# APM32F030K8T6.net
KiCad netlist of a schematic drawn in Altium Designer
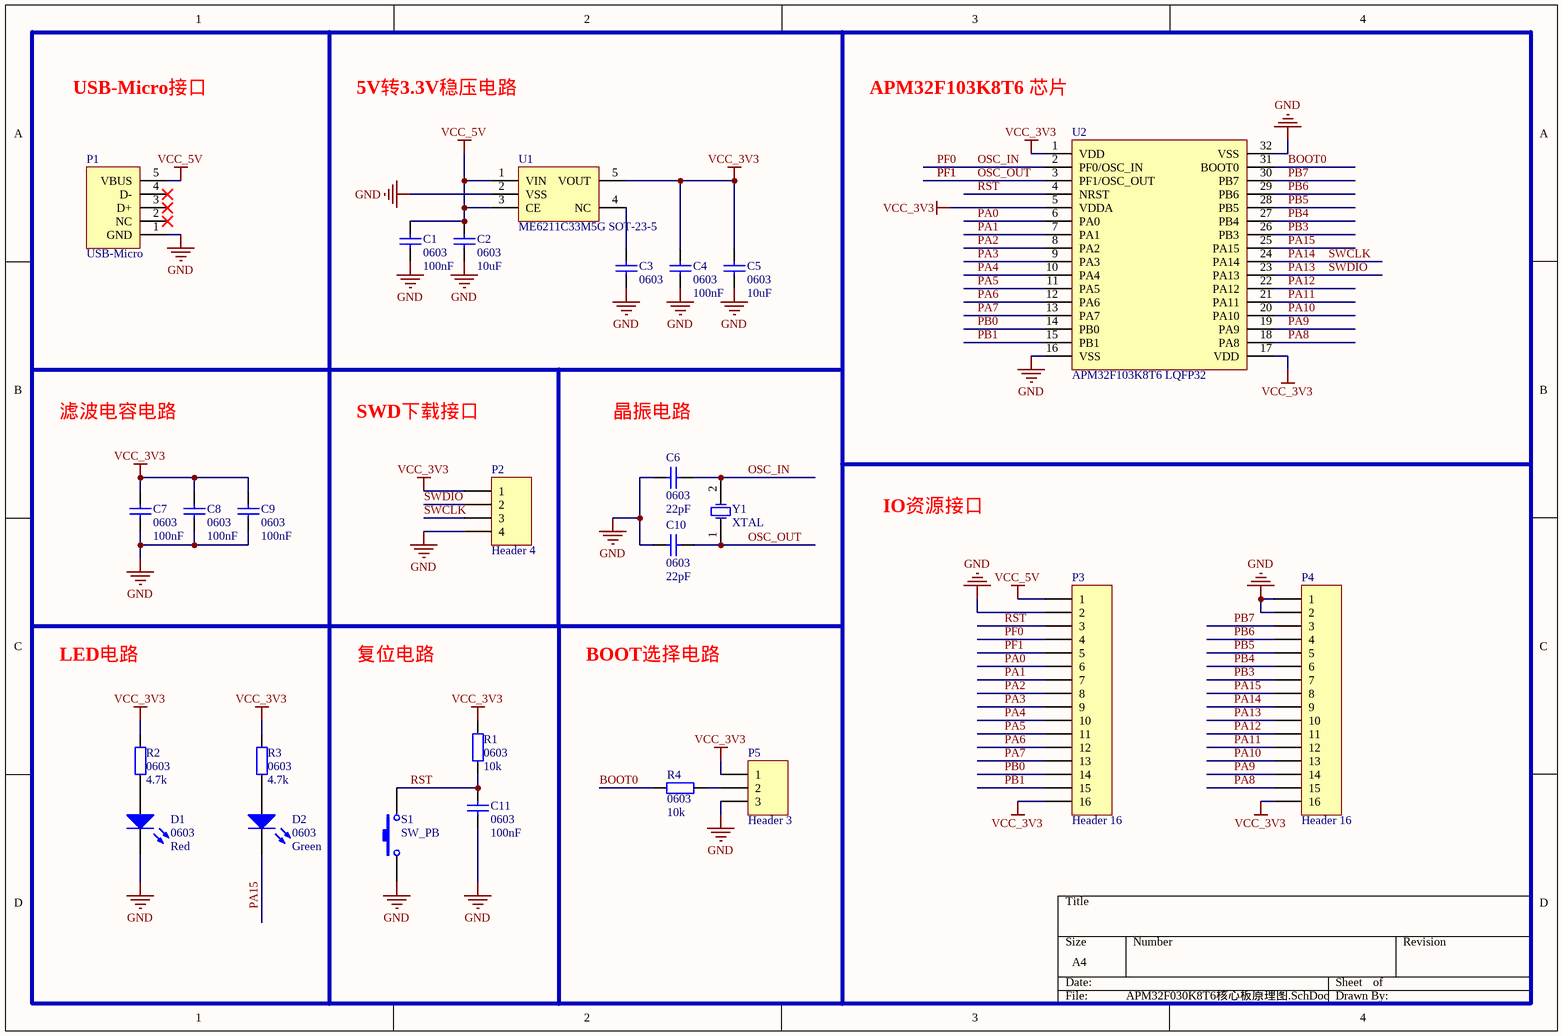
[diagram p0: APM32F030K8T6核心板原理图.SchDoc]

(export (version "E")
  (design (tool "Eeschema 10.0.6"))
  (components
    (comp (ref "C1")
      (value "100nF")
      (footprint "0603")
      (description "Capacitor 0603")
      (fields (field (name "Comment") "Cap 0603"))
      (libsource (lib "Schlib1") (part "Cap 0603"))
    )
    (comp (ref "C2")
      (value "10uF")
      (footprint "0603")
      (description "Capacitor 0603")
      (fields (field (name "Comment") "Cap 0603"))
      (libsource (lib "Schlib1") (part "Cap 0603"))
    )
    (comp (ref "C3")
      (value "Cap 0603")
      (footprint "0603")
      (description "Capacitor 0603")
      (libsource (lib "Schlib1") (part "Cap 0603"))
    )
    (comp (ref "C4")
      (value "100nF")
      (footprint "0603")
      (description "Capacitor 0603")
      (fields (field (name "Comment") "Cap 0603"))
      (libsource (lib "Schlib1") (part "Cap 0603"))
    )
    (comp (ref "C5")
      (value "10uF")
      (footprint "0603")
      (description "Capacitor 0603")
      (fields (field (name "Comment") "Cap 0603"))
      (libsource (lib "Schlib1") (part "Cap 0603"))
    )
    (comp (ref "C6")
      (value "22pF")
      (footprint "0603")
      (description "Capacitor 0603")
      (fields (field (name "Comment") "Cap 0603"))
      (libsource (lib "Schlib1") (part "Cap 0603"))
    )
    (comp (ref "C7")
      (value "100nF")
      (footprint "0603")
      (description "Capacitor 0603")
      (fields (field (name "Comment") "Cap 0603"))
      (libsource (lib "Schlib1") (part "Cap 0603"))
    )
    (comp (ref "C8")
      (value "100nF")
      (footprint "0603")
      (description "Capacitor 0603")
      (fields (field (name "Comment") "Cap 0603"))
      (libsource (lib "Schlib1") (part "Cap 0603"))
    )
    (comp (ref "C9")
      (value "100nF")
      (footprint "0603")
      (description "Capacitor 0603")
      (fields (field (name "Comment") "Cap 0603"))
      (libsource (lib "Schlib1") (part "Cap 0603"))
    )
    (comp (ref "C10")
      (value "22pF")
      (footprint "0603")
      (description "Capacitor 0603")
      (fields (field (name "Comment") "Cap 0603"))
      (libsource (lib "Schlib1") (part "Cap 0603"))
    )
    (comp (ref "C11")
      (value "100nF")
      (footprint "0603")
      (description "Capacitor 0603")
      (fields (field (name "Comment") "Cap 0603"))
      (libsource (lib "Schlib1") (part "Cap 0603"))
    )
    (comp (ref "D1")
      (value "Red")
      (footprint "0603")
      (description "LED 0603")
      (libsource (lib "Schlib1") (part "LED 0603"))
    )
    (comp (ref "D2")
      (value "Green")
      (footprint "0603")
      (description "LED 0603")
      (libsource (lib "Schlib1") (part "LED 0603"))
    )
    (comp (ref "P1")
      (value "USB-Micro")
      (footprint "USB Micro")
      (libsource (lib "Schlib1") (part "USB-Micro"))
    )
    (comp (ref "P2")
      (value "Header 4")
      (footprint "HDR1X4")
      (description "Header, 4-Pin")
      (fields (field (name "PUBLISHER") "Altium Limited"))
      (libsource (lib "Miscellaneous Connectors") (part "Header 4"))
    )
    (comp (ref "P3")
      (value "Header 16")
      (footprint "HDR1X16")
      (description "Header, 16-Pin")
      (fields (field (name "PUBLISHER") "Altium Limited"))
      (libsource (lib "Miscellaneous Connectors") (part "Header 16"))
    )
    (comp (ref "P4")
      (value "Header 16")
      (footprint "HDR1X16")
      (description "Header, 16-Pin")
      (fields (field (name "PUBLISHER") "Altium Limited"))
      (libsource (lib "Miscellaneous Connectors") (part "Header 16"))
    )
    (comp (ref "P5")
      (value "Header 3")
      (footprint "HDR1X3")
      (description "Header, 3-Pin")
      (fields (field (name "PUBLISHER") "Altium Limited"))
      (libsource (lib "Miscellaneous Connectors") (part "Header 3"))
    )
    (comp (ref "R1")
      (value "10k")
      (footprint "0603")
      (description "Resistor 0603")
      (fields (field (name "Comment") "Res 0603"))
      (libsource (lib "") (part "Res 0603_2"))
    )
    (comp (ref "R2")
      (value "4.7k")
      (footprint "0603")
      (description "Resistor 0603")
      (fields (field (name "Comment") "Res 0603"))
      (libsource (lib "") (part "Res 0603_1"))
    )
    (comp (ref "R3")
      (value "4.7k")
      (footprint "0603")
      (description "Resistor 0603")
      (fields (field (name "Comment") "Res 0603"))
      (libsource (lib "") (part "Res 0603_1"))
    )
    (comp (ref "R4")
      (value "10k")
      (footprint "0603")
      (description "Resistor 0603")
      (fields (field (name "Comment") "Res 0603"))
      (libsource (lib "Schlib1") (part "Res 0603"))
    )
    (comp (ref "S1") (value "SW_PB") (footprint "SW-2Pin") (libsource (lib "Schlib1") (part "SW_PB")))
    (comp (ref "U1")
      (value "ME6211C33M5G SOT-23-5")
      (footprint "SOT-23-5")
      (libsource (lib "Schlib1") (part "ME6211C33M5G"))
    )
    (comp (ref "U2")
      (value "APM32F103K8T6 LQFP32")
      (footprint "QFP32_M")
      (description "STM32F030K6T6 LQFP32")
      (libsource (lib "Schlib1") (part "STM32F030K6T6 LQFP32"))
    )
    (comp (ref "Y1")
      (value "XTAL")
      (footprint "XTAL_5032")
      (description "XTAL 8MHZ")
      (libsource (lib "Schlib1") (part "XTAL 8MHZ"))
    )
  )
  (nets
    (net (code "1") (name "/BOOT0") (class "Default")
      (node (ref "R4") (pin "1") (pinfunction "1_1") (pintype "passive"))
      (node (ref "U2") (pin "31") (pinfunction "BOOT0_31") (pintype "power_in"))
    )
    (net (code "2") (name "/OSC_IN") (class "Default")
      (node (ref "C6") (pin "1") (pinfunction "1_1") (pintype "passive"))
      (node (ref "P3") (pin "4") (pinfunction "4_4") (pintype "passive"))
      (node (ref "U2") (pin "2") (pinfunction "PF0/OSC_IN_2") (pintype "power_in"))
      (node (ref "Y1") (pin "2") (pinfunction "OSC2_2") (pintype "passive"))
    )
    (net (code "3") (name "/OSC_OUT") (class "Default")
      (node (ref "C10") (pin "1") (pinfunction "1_1") (pintype "passive"))
      (node (ref "P3") (pin "5") (pinfunction "5_5") (pintype "passive"))
      (node (ref "U2") (pin "3") (pinfunction "PF1/OSC_OUT_3") (pintype "power_in"))
      (node (ref "Y1") (pin "1") (pinfunction "OSC1_1") (pintype "passive"))
    )
    (net (code "4") (name "/PA0") (class "Default")
      (node (ref "P3") (pin "6") (pinfunction "6_6") (pintype "passive"))
      (node (ref "U2") (pin "6") (pinfunction "PA0_6") (pintype "power_in"))
    )
    (net (code "5") (name "/PA1") (class "Default")
      (node (ref "P3") (pin "7") (pinfunction "7_7") (pintype "passive"))
      (node (ref "U2") (pin "7") (pinfunction "PA1_7") (pintype "power_in"))
    )
    (net (code "6") (name "/PA2") (class "Default")
      (node (ref "P3") (pin "8") (pinfunction "8_8") (pintype "passive"))
      (node (ref "U2") (pin "8") (pinfunction "PA2_8") (pintype "power_in"))
    )
    (net (code "7") (name "/PA3") (class "Default")
      (node (ref "P3") (pin "9") (pinfunction "9_9") (pintype "passive"))
      (node (ref "U2") (pin "9") (pinfunction "PA3_9") (pintype "power_in"))
    )
    (net (code "8") (name "/PA4") (class "Default")
      (node (ref "P3") (pin "10") (pinfunction "10_10") (pintype "passive"))
      (node (ref "U2") (pin "10") (pinfunction "PA4_10") (pintype "power_in"))
    )
    (net (code "9") (name "/PA5") (class "Default")
      (node (ref "P3") (pin "11") (pinfunction "11_11") (pintype "passive"))
      (node (ref "U2") (pin "11") (pinfunction "PA5_11") (pintype "power_in"))
    )
    (net (code "10") (name "/PA6") (class "Default")
      (node (ref "P3") (pin "12") (pinfunction "12_12") (pintype "passive"))
      (node (ref "U2") (pin "12") (pinfunction "PA6_12") (pintype "power_in"))
    )
    (net (code "11") (name "/PA7") (class "Default")
      (node (ref "P3") (pin "13") (pinfunction "13_13") (pintype "passive"))
      (node (ref "U2") (pin "13") (pinfunction "PA7_13") (pintype "power_in"))
    )
    (net (code "12") (name "/PA8") (class "Default")
      (node (ref "P4") (pin "15") (pinfunction "15_15") (pintype "passive"))
      (node (ref "U2") (pin "18") (pinfunction "PA8_18") (pintype "power_in"))
    )
    (net (code "13") (name "/PA9") (class "Default")
      (node (ref "P4") (pin "14") (pinfunction "14_14") (pintype "passive"))
      (node (ref "U2") (pin "19") (pinfunction "PA9_19") (pintype "power_in"))
    )
    (net (code "14") (name "/PA10") (class "Default")
      (node (ref "P4") (pin "13") (pinfunction "13_13") (pintype "passive"))
      (node (ref "U2") (pin "20") (pinfunction "PA10_20") (pintype "power_in"))
    )
    (net (code "15") (name "/PA11") (class "Default")
      (node (ref "P4") (pin "12") (pinfunction "12_12") (pintype "passive"))
      (node (ref "U2") (pin "21") (pinfunction "PA11_21") (pintype "power_in"))
    )
    (net (code "16") (name "/PA12") (class "Default")
      (node (ref "P4") (pin "11") (pinfunction "11_11") (pintype "passive"))
      (node (ref "U2") (pin "22") (pinfunction "PA12_22") (pintype "power_in"))
    )
    (net (code "17") (name "/PA13") (class "Default")
      (node (ref "P2") (pin "2") (pinfunction "2_2") (pintype "passive"))
      (node (ref "P4") (pin "10") (pinfunction "10_10") (pintype "passive"))
      (node (ref "U2") (pin "23") (pinfunction "PA13_23") (pintype "power_in"))
    )
    (net (code "18") (name "/PA14") (class "Default")
      (node (ref "P2") (pin "3") (pinfunction "3_3") (pintype "passive"))
      (node (ref "P4") (pin "9") (pinfunction "9_9") (pintype "passive"))
      (node (ref "U2") (pin "24") (pinfunction "PA14_24") (pintype "power_in"))
    )
    (net (code "19") (name "/PA15") (class "Default")
      (node (ref "D2") (pin "2") (pinfunction "K_2") (pintype "passive"))
      (node (ref "P4") (pin "8") (pinfunction "8_8") (pintype "passive"))
      (node (ref "U2") (pin "25") (pinfunction "PA15_25") (pintype "power_in"))
    )
    (net (code "20") (name "/PB0") (class "Default")
      (node (ref "P3") (pin "14") (pinfunction "14_14") (pintype "passive"))
      (node (ref "U2") (pin "14") (pinfunction "PB0_14") (pintype "power_in"))
    )
    (net (code "21") (name "/PB1") (class "Default")
      (node (ref "P3") (pin "15") (pinfunction "15_15") (pintype "passive"))
      (node (ref "U2") (pin "15") (pinfunction "PB1_15") (pintype "power_in"))
    )
    (net (code "22") (name "/PB3") (class "Default")
      (node (ref "P4") (pin "7") (pinfunction "7_7") (pintype "passive"))
      (node (ref "U2") (pin "26") (pinfunction "PB3_26") (pintype "power_in"))
    )
    (net (code "23") (name "/PB4") (class "Default")
      (node (ref "P4") (pin "6") (pinfunction "6_6") (pintype "passive"))
      (node (ref "U2") (pin "27") (pinfunction "PB4_27") (pintype "power_in"))
    )
    (net (code "24") (name "/PB5") (class "Default")
      (node (ref "P4") (pin "5") (pinfunction "5_5") (pintype "passive"))
      (node (ref "U2") (pin "28") (pinfunction "PB5_28") (pintype "power_in"))
    )
    (net (code "25") (name "/PB6") (class "Default")
      (node (ref "P4") (pin "4") (pinfunction "4_4") (pintype "passive"))
      (node (ref "U2") (pin "29") (pinfunction "PB6_29") (pintype "power_in"))
    )
    (net (code "26") (name "/PB7") (class "Default")
      (node (ref "P4") (pin "3") (pinfunction "3_3") (pintype "passive"))
      (node (ref "U2") (pin "30") (pinfunction "PB7_30") (pintype "power_in"))
    )
    (net (code "27") (name "/RST") (class "Default")
      (node (ref "C11") (pin "2") (pinfunction "2_2") (pintype "passive"))
      (node (ref "P3") (pin "3") (pinfunction "3_3") (pintype "passive"))
      (node (ref "R1") (pin "1") (pinfunction "1_1") (pintype "passive"))
      (node (ref "S1") (pin "2") (pinfunction "2_2") (pintype "passive"))
      (node (ref "U2") (pin "4") (pinfunction "NRST_4") (pintype "power_in"))
    )
    (net (code "28") (name "GND") (class "Default")
      (node (ref "C1") (pin "1") (pinfunction "1_1") (pintype "passive"))
      (node (ref "C10") (pin "2") (pinfunction "2_2") (pintype "passive"))
      (node (ref "C11") (pin "1") (pinfunction "1_1") (pintype "passive"))
      (node (ref "C2") (pin "1") (pinfunction "1_1") (pintype "passive"))
      (node (ref "C3") (pin "1") (pinfunction "1_1") (pintype "passive"))
      (node (ref "C4") (pin "1") (pinfunction "1_1") (pintype "passive"))
      (node (ref "C5") (pin "1") (pinfunction "1_1") (pintype "passive"))
      (node (ref "C6") (pin "2") (pinfunction "2_2") (pintype "passive"))
      (node (ref "C7") (pin "1") (pinfunction "1_1") (pintype "passive"))
      (node (ref "C8") (pin "1") (pinfunction "1_1") (pintype "passive"))
      (node (ref "C9") (pin "1") (pinfunction "1_1") (pintype "passive"))
      (node (ref "D1") (pin "2") (pinfunction "K_2") (pintype "passive"))
      (node (ref "P1") (pin "1") (pinfunction "GND_1") (pintype "power_in"))
      (node (ref "P2") (pin "4") (pinfunction "4_4") (pintype "passive"))
      (node (ref "P3") (pin "2") (pinfunction "2_2") (pintype "passive"))
      (node (ref "P4") (pin "1") (pinfunction "1_1") (pintype "passive"))
      (node (ref "P4") (pin "2") (pinfunction "2_2") (pintype "passive"))
      (node (ref "P5") (pin "3") (pinfunction "3_3") (pintype "passive"))
      (node (ref "S1") (pin "1") (pinfunction "1_1") (pintype "passive"))
      (node (ref "U1") (pin "2") (pinfunction "VSS_2") (pintype "power_in"))
      (node (ref "U2") (pin "16") (pinfunction "VSS_16") (pintype "power_in"))
      (node (ref "U2") (pin "32") (pinfunction "VSS_32") (pintype "power_in"))
    )
    (net (code "29") (name "Net-(D1-A)") (class "Default")
      (node (ref "D1") (pin "1") (pinfunction "A_1") (pintype "passive"))
      (node (ref "R2") (pin "2") (pinfunction "2_2") (pintype "passive"))
    )
    (net (code "30") (name "Net-(D2-A)") (class "Default")
      (node (ref "D2") (pin "1") (pinfunction "A_1") (pintype "passive"))
      (node (ref "R3") (pin "2") (pinfunction "2_2") (pintype "passive"))
    )
    (net (code "31") (name "Net-(P5-Pad2)") (class "Default")
      (node (ref "P5") (pin "2") (pinfunction "2_2") (pintype "passive"))
      (node (ref "R4") (pin "2") (pinfunction "2_2") (pintype "passive"))
    )
    (net (code "32") (name "Net-(U1-NC)") (class "Default")
      (node (ref "C3") (pin "2") (pinfunction "2_2") (pintype "passive"))
      (node (ref "U1") (pin "4") (pinfunction "NC_4") (pintype "power_in"))
    )
    (net (code "33") (name "VCC_3V3") (class "Default")
      (node (ref "C4") (pin "2") (pinfunction "2_2") (pintype "passive"))
      (node (ref "C5") (pin "2") (pinfunction "2_2") (pintype "passive"))
      (node (ref "C7") (pin "2") (pinfunction "2_2") (pintype "passive"))
      (node (ref "C8") (pin "2") (pinfunction "2_2") (pintype "passive"))
      (node (ref "C9") (pin "2") (pinfunction "2_2") (pintype "passive"))
      (node (ref "P2") (pin "1") (pinfunction "1_1") (pintype "passive"))
      (node (ref "P3") (pin "16") (pinfunction "16_16") (pintype "passive"))
      (node (ref "P4") (pin "16") (pinfunction "16_16") (pintype "passive"))
      (node (ref "P5") (pin "1") (pinfunction "1_1") (pintype "passive"))
      (node (ref "R1") (pin "2") (pinfunction "2_2") (pintype "passive"))
      (node (ref "R2") (pin "1") (pinfunction "1_1") (pintype "passive"))
      (node (ref "R3") (pin "1") (pinfunction "1_1") (pintype "passive"))
      (node (ref "U1") (pin "5") (pinfunction "VOUT_5") (pintype "power_in"))
      (node (ref "U2") (pin "1") (pinfunction "VDD_1") (pintype "power_in"))
      (node (ref "U2") (pin "17") (pinfunction "VDD_17") (pintype "power_in"))
      (node (ref "U2") (pin "5") (pinfunction "VDDA_5") (pintype "power_in"))
    )
    (net (code "34") (name "VCC_5V") (class "Default")
      (node (ref "C1") (pin "2") (pinfunction "2_2") (pintype "passive"))
      (node (ref "C2") (pin "2") (pinfunction "2_2") (pintype "passive"))
      (node (ref "P1") (pin "5") (pinfunction "VBUS_5") (pintype "power_in"))
      (node (ref "P3") (pin "1") (pinfunction "1_1") (pintype "passive"))
      (node (ref "U1") (pin "1") (pinfunction "VIN_1") (pintype "power_in"))
      (node (ref "U1") (pin "3") (pinfunction "CE_3") (pintype "power_in"))
    )
    (net (code "35") (name "unconnected-(P1-D+-Pad3)") (class "Default")
      (node (ref "P1") (pin "3") (pinfunction "D+_3") (pintype "power_in+no_connect"))
    )
    (net (code "36") (name "unconnected-(P1-D--Pad4)") (class "Default")
      (node (ref "P1") (pin "4") (pinfunction "D-_4") (pintype "power_in+no_connect"))
    )
    (net (code "37") (name "unconnected-(P1-NC-Pad2)") (class "Default")
      (node (ref "P1") (pin "2") (pinfunction "NC_2") (pintype "power_in+no_connect"))
    )
  )
)
